# design.net
KiCad netlist of a schematic drawn in Altium Designer
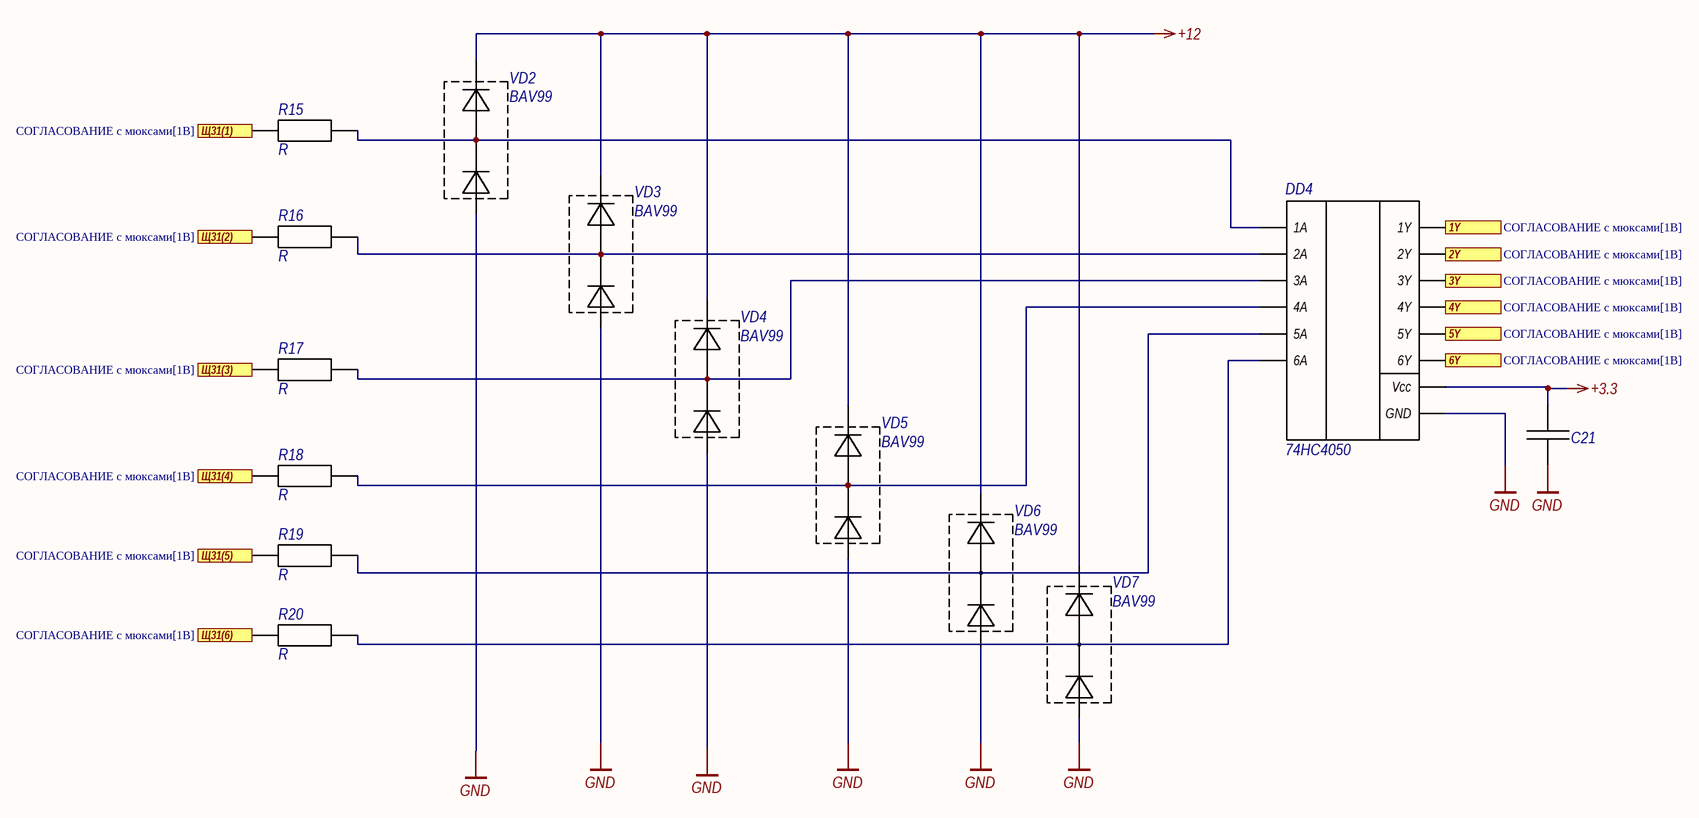
[diagram p0: ВХ Б (1-6).SchDoc]

(export (version "E")
  (design (tool "Eeschema 10.0.6"))
  (components
    (comp (ref "C21")
      (value "C(ceramic)")
      (footprint "C(ceramic)")
      (libsource (lib "UGO") (part "C(ceramic)"))
    )
    (comp (ref "DD4") (value "74HC4050") (footprint "74HC4050(51)") (libsource (lib "UGO") (part "74HC4050")))
    (comp (ref "R15") (value "R") (footprint "R") (libsource (lib "UGO") (part "R")))
    (comp (ref "R16") (value "R") (footprint "R") (libsource (lib "UGO") (part "R")))
    (comp (ref "R17") (value "R") (footprint "R") (libsource (lib "UGO") (part "R")))
    (comp (ref "R18") (value "R") (footprint "R") (libsource (lib "UGO") (part "R")))
    (comp (ref "R19") (value "R") (footprint "R") (libsource (lib "UGO") (part "R")))
    (comp (ref "R20") (value "R") (footprint "R") (libsource (lib "UGO") (part "R")))
    (comp (ref "VD2") (value "BAV99") (footprint "BAV99") (libsource (lib "UGO") (part "BAV99")))
    (comp (ref "VD3") (value "BAV99") (footprint "BAV99") (libsource (lib "") (part "BAV99_1")))
    (comp (ref "VD4") (value "BAV99") (footprint "BAV99") (libsource (lib "UGO") (part "BAV99")))
    (comp (ref "VD5") (value "BAV99") (footprint "BAV99") (libsource (lib "UGO") (part "BAV99")))
    (comp (ref "VD6") (value "BAV99") (footprint "BAV99") (libsource (lib "UGO") (part "BAV99")))
    (comp (ref "VD7") (value "BAV99") (footprint "BAV99") (libsource (lib "UGO") (part "BAV99")))
  )
  (nets
    (net (code "1") (name "+3.3") (class "Default")
      (node (ref "C21") (pin "1") (pintype "passive"))
      (node (ref "DD4") (pin "1") (pinfunction "Vcc_1") (pintype "passive"))
    )
    (net (code "2") (name "+12") (class "Default")
      (node (ref "VD2") (pin "2") (pintype "passive"))
      (node (ref "VD3") (pin "2") (pintype "passive"))
      (node (ref "VD4") (pin "2") (pintype "passive"))
      (node (ref "VD5") (pin "2") (pintype "passive"))
      (node (ref "VD6") (pin "2") (pintype "passive"))
      (node (ref "VD7") (pin "2") (pintype "passive"))
    )
    (net (code "3") (name "/1Y") (class "Default")
      (node (ref "DD4") (pin "2") (pinfunction "1Y_2") (pintype "passive"))
    )
    (net (code "4") (name "/2Y") (class "Default")
      (node (ref "DD4") (pin "4") (pinfunction "2Y_4") (pintype "passive"))
    )
    (net (code "5") (name "/3Y") (class "Default")
      (node (ref "DD4") (pin "6") (pinfunction "3Y_6") (pintype "passive"))
    )
    (net (code "6") (name "/4Y") (class "Default")
      (node (ref "DD4") (pin "10") (pinfunction "4Y_10") (pintype "passive"))
    )
    (net (code "7") (name "/5Y") (class "Default")
      (node (ref "DD4") (pin "12") (pinfunction "5Y_12") (pintype "passive"))
    )
    (net (code "8") (name "/6Y") (class "Default")
      (node (ref "DD4") (pin "15") (pinfunction "6Y_15") (pintype "passive"))
    )
    (net (code "9") (name "/Щ31(1)") (class "Default") (node (ref "R15") (pin "1") (pintype "passive")))
    (net (code "10") (name "/Щ31(2)") (class "Default") (node (ref "R16") (pin "1") (pintype "passive")))
    (net (code "11") (name "/Щ31(3)") (class "Default") (node (ref "R17") (pin "1") (pintype "passive")))
    (net (code "12") (name "/Щ31(4)") (class "Default") (node (ref "R18") (pin "1") (pintype "passive")))
    (net (code "13") (name "/Щ31(5)") (class "Default") (node (ref "R19") (pin "1") (pintype "passive")))
    (net (code "14") (name "/Щ31(6)") (class "Default") (node (ref "R20") (pin "1") (pintype "passive")))
    (net (code "15") (name "GND") (class "Default")
      (node (ref "C21") (pin "2") (pintype "passive"))
      (node (ref "DD4") (pin "8") (pinfunction "GND_8") (pintype "passive"))
      (node (ref "VD2") (pin "1") (pintype "passive"))
      (node (ref "VD3") (pin "1") (pintype "passive"))
      (node (ref "VD4") (pin "1") (pintype "passive"))
      (node (ref "VD5") (pin "1") (pintype "passive"))
      (node (ref "VD6") (pin "1") (pintype "passive"))
      (node (ref "VD7") (pin "1") (pintype "passive"))
    )
    (net (code "16") (name "Net-(DD4-1A)") (class "Default")
      (node (ref "DD4") (pin "3") (pinfunction "1A_3") (pintype "passive"))
      (node (ref "R15") (pin "2") (pintype "passive"))
      (node (ref "VD2") (pin "3") (pintype "passive"))
    )
    (net (code "17") (name "Net-(DD4-2A)") (class "Default")
      (node (ref "DD4") (pin "5") (pinfunction "2A_5") (pintype "passive"))
      (node (ref "R16") (pin "2") (pintype "passive"))
      (node (ref "VD3") (pin "3") (pintype "passive"))
    )
    (net (code "18") (name "Net-(DD4-3A)") (class "Default")
      (node (ref "DD4") (pin "7") (pinfunction "3A_7") (pintype "passive"))
      (node (ref "R17") (pin "2") (pintype "passive"))
      (node (ref "VD4") (pin "3") (pintype "passive"))
    )
    (net (code "19") (name "Net-(DD4-4A)") (class "Default")
      (node (ref "DD4") (pin "9") (pinfunction "4A_9") (pintype "passive"))
      (node (ref "R18") (pin "2") (pintype "passive"))
      (node (ref "VD5") (pin "3") (pintype "passive"))
    )
    (net (code "20") (name "Net-(DD4-5A)") (class "Default")
      (node (ref "DD4") (pin "11") (pinfunction "5A_11") (pintype "passive"))
      (node (ref "R19") (pin "2") (pintype "passive"))
      (node (ref "VD6") (pin "3") (pintype "passive"))
    )
    (net (code "21") (name "Net-(DD4-6A)") (class "Default")
      (node (ref "DD4") (pin "14") (pinfunction "6A_14") (pintype "passive"))
      (node (ref "R20") (pin "2") (pintype "passive"))
      (node (ref "VD7") (pin "3") (pintype "passive"))
    )
  )
)
